# TFTProtoBreakout.net
KiCad netlist of a schematic drawn in EAGLE
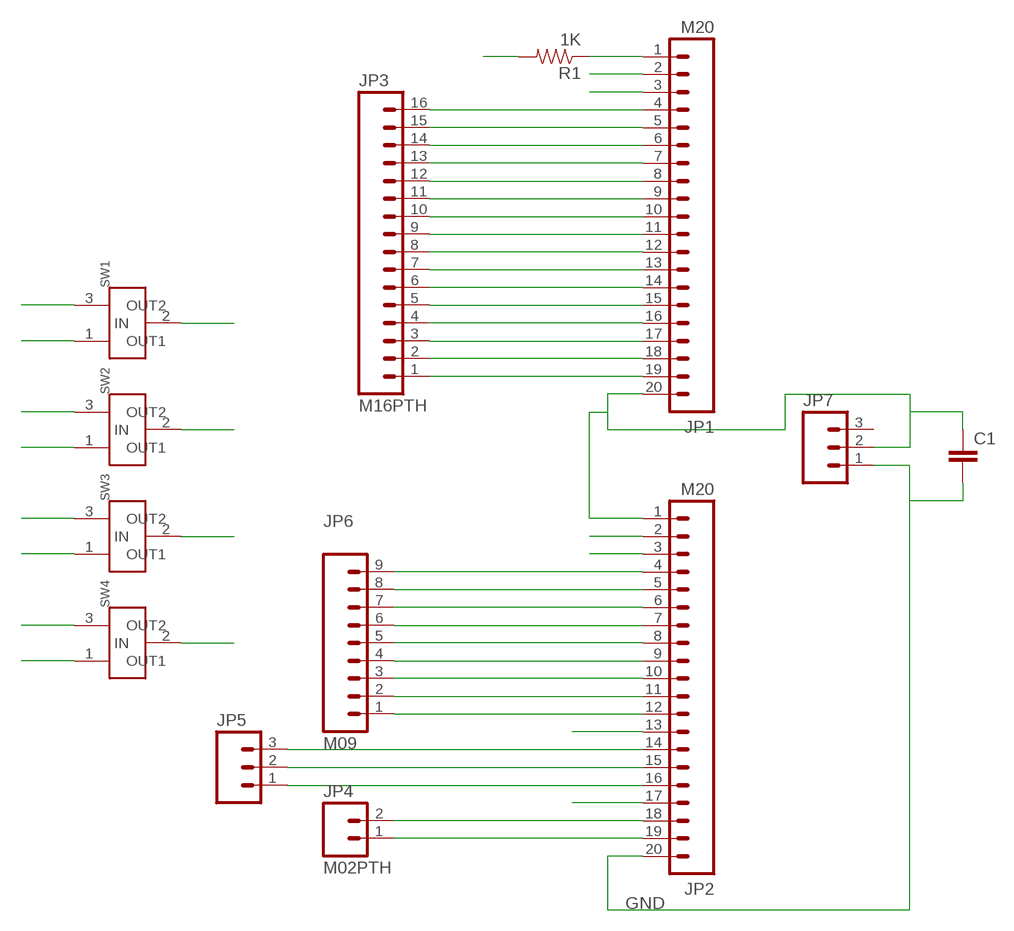
[diagram p0: schematic, sheet 1]

(export (version "E")
  (design (tool "Eeschema 10.0.6"))
  (components
    (comp (ref "C1")
      (value "CAP0805")
      (footprint "eagle-import:0805")
      (libsource (lib "eagle-import") (part "CAP0805"))
    )
    (comp (ref "JP1")
      (value "M20")
      (footprint "eagle-import:1X20")
      (libsource (lib "eagle-import") (part "M20"))
    )
    (comp (ref "JP2")
      (value "M20")
      (footprint "eagle-import:1X20")
      (libsource (lib "eagle-import") (part "M20"))
    )
    (comp (ref "JP3")
      (value "M16PTH")
      (footprint "eagle-import:1X16")
      (libsource (lib "eagle-import") (part "M16PTH"))
    )
    (comp (ref "JP4")
      (value "M02PTH")
      (footprint "eagle-import:1X02")
      (libsource (lib "eagle-import") (part "M02PTH"))
    )
    (comp (ref "JP5")
      (value "M03PTH")
      (footprint "eagle-import:1X03")
      (libsource (lib "eagle-import") (part "M03PTH"))
    )
    (comp (ref "JP6")
      (value "M09")
      (footprint "eagle-import:1X09")
      (libsource (lib "eagle-import") (part "M09"))
    )
    (comp (ref "JP7")
      (value "M03PTH")
      (footprint "eagle-import:1X03")
      (libsource (lib "eagle-import") (part "M03PTH"))
    )
    (comp (ref "R1")
      (value "1K")
      (footprint "eagle-import:0603-RES")
      (libsource (lib "eagle-import") (part "1KOHM1/10W1%(0603)"))
    )
    (comp (ref "SW1")
      (value "PCM12SMTR")
      (footprint "eagle-import:PCM12SMTR")
      (libsource (lib "eagle-import") (part "PCM12SMTR"))
    )
    (comp (ref "SW2")
      (value "PCM12SMTR")
      (footprint "eagle-import:PCM12SMTR")
      (libsource (lib "eagle-import") (part "PCM12SMTR"))
    )
    (comp (ref "SW3")
      (value "PCM12SMTR")
      (footprint "eagle-import:PCM12SMTR")
      (libsource (lib "eagle-import") (part "PCM12SMTR"))
    )
    (comp (ref "SW4")
      (value "PCM12SMTR")
      (footprint "eagle-import:PCM12SMTR")
      (libsource (lib "eagle-import") (part "PCM12SMTR"))
    )
  )
  (nets
    (net (code "1") (name "/GND") (class "Default")
      (node (ref "C1") (pin "2") (pinfunction "2_2") (pintype "passive"))
      (node (ref "JP2") (pin "13") (pinfunction "13_13") (pintype "passive"))
      (node (ref "JP2") (pin "17") (pinfunction "17_17") (pintype "passive"))
      (node (ref "JP2") (pin "20") (pinfunction "20_20") (pintype "passive"))
      (node (ref "JP7") (pin "1") (pinfunction "1_1") (pintype "passive"))
      (node (ref "R1") (pin "2") (pinfunction "2_2") (pintype "passive"))
      (node (ref "SW1") (pin "1") (pinfunction "OUT1_1") (pintype "bidirectional"))
      (node (ref "SW2") (pin "1") (pinfunction "OUT1_1") (pintype "bidirectional"))
      (node (ref "SW3") (pin "1") (pinfunction "OUT1_1") (pintype "bidirectional"))
      (node (ref "SW4") (pin "1") (pinfunction "OUT1_1") (pintype "bidirectional"))
    )
    (net (code "2") (name "/IM0") (class "Default")
      (node (ref "JP1") (pin "2") (pinfunction "2_2") (pintype "passive"))
      (node (ref "SW1") (pin "2") (pinfunction "IN_2") (pintype "bidirectional"))
    )
    (net (code "3") (name "/IM1") (class "Default")
      (node (ref "JP2") (pin "2") (pinfunction "2_2") (pintype "passive"))
      (node (ref "SW2") (pin "2") (pinfunction "IN_2") (pintype "bidirectional"))
    )
    (net (code "4") (name "/IM2") (class "Default")
      (node (ref "JP1") (pin "3") (pinfunction "3_3") (pintype "passive"))
      (node (ref "SW3") (pin "2") (pinfunction "IN_2") (pintype "bidirectional"))
    )
    (net (code "5") (name "/IM3") (class "Default")
      (node (ref "JP2") (pin "3") (pinfunction "3_3") (pintype "passive"))
      (node (ref "SW4") (pin "2") (pinfunction "IN_2") (pintype "bidirectional"))
    )
    (net (code "6") (name "/VCC") (class "Default")
      (node (ref "C1") (pin "1") (pinfunction "1_1") (pintype "passive"))
      (node (ref "JP1") (pin "20") (pinfunction "20_20") (pintype "passive"))
      (node (ref "JP2") (pin "1") (pinfunction "1_1") (pintype "passive"))
      (node (ref "JP7") (pin "2") (pinfunction "2_2") (pintype "passive"))
      (node (ref "SW1") (pin "3") (pinfunction "OUT2_3") (pintype "bidirectional"))
      (node (ref "SW2") (pin "3") (pinfunction "OUT2_3") (pintype "bidirectional"))
      (node (ref "SW3") (pin "3") (pinfunction "OUT2_3") (pintype "bidirectional"))
      (node (ref "SW4") (pin "3") (pinfunction "OUT2_3") (pintype "bidirectional"))
    )
    (net (code "7") (name "Net-(JP1-Pad1)") (class "Default")
      (node (ref "JP1") (pin "1") (pinfunction "1_1") (pintype "passive"))
      (node (ref "R1") (pin "1") (pinfunction "1_1") (pintype "passive"))
    )
    (net (code "8") (name "Net-(JP1-Pad4)") (class "Default")
      (node (ref "JP1") (pin "4") (pinfunction "4_4") (pintype "passive"))
      (node (ref "JP3") (pin "16") (pinfunction "16_16") (pintype "passive"))
    )
    (net (code "9") (name "Net-(JP1-Pad5)") (class "Default")
      (node (ref "JP1") (pin "5") (pinfunction "5_5") (pintype "passive"))
      (node (ref "JP3") (pin "15") (pinfunction "15_15") (pintype "passive"))
    )
    (net (code "10") (name "Net-(JP1-Pad6)") (class "Default")
      (node (ref "JP1") (pin "6") (pinfunction "6_6") (pintype "passive"))
      (node (ref "JP3") (pin "14") (pinfunction "14_14") (pintype "passive"))
    )
    (net (code "11") (name "Net-(JP1-Pad7)") (class "Default")
      (node (ref "JP1") (pin "7") (pinfunction "7_7") (pintype "passive"))
      (node (ref "JP3") (pin "13") (pinfunction "13_13") (pintype "passive"))
    )
    (net (code "12") (name "Net-(JP1-Pad8)") (class "Default")
      (node (ref "JP1") (pin "8") (pinfunction "8_8") (pintype "passive"))
      (node (ref "JP3") (pin "12") (pinfunction "12_12") (pintype "passive"))
    )
    (net (code "13") (name "Net-(JP1-Pad9)") (class "Default")
      (node (ref "JP1") (pin "9") (pinfunction "9_9") (pintype "passive"))
      (node (ref "JP3") (pin "11") (pinfunction "11_11") (pintype "passive"))
    )
    (net (code "14") (name "Net-(JP1-Pad10)") (class "Default")
      (node (ref "JP1") (pin "10") (pinfunction "10_10") (pintype "passive"))
      (node (ref "JP3") (pin "10") (pinfunction "10_10") (pintype "passive"))
    )
    (net (code "15") (name "Net-(JP1-Pad11)") (class "Default")
      (node (ref "JP1") (pin "11") (pinfunction "11_11") (pintype "passive"))
      (node (ref "JP3") (pin "9") (pinfunction "9_9") (pintype "passive"))
    )
    (net (code "16") (name "Net-(JP1-Pad12)") (class "Default")
      (node (ref "JP1") (pin "12") (pinfunction "12_12") (pintype "passive"))
      (node (ref "JP3") (pin "8") (pinfunction "8_8") (pintype "passive"))
    )
    (net (code "17") (name "Net-(JP1-Pad13)") (class "Default")
      (node (ref "JP1") (pin "13") (pinfunction "13_13") (pintype "passive"))
      (node (ref "JP3") (pin "7") (pinfunction "7_7") (pintype "passive"))
    )
    (net (code "18") (name "Net-(JP1-Pad14)") (class "Default")
      (node (ref "JP1") (pin "14") (pinfunction "14_14") (pintype "passive"))
      (node (ref "JP3") (pin "6") (pinfunction "6_6") (pintype "passive"))
    )
    (net (code "19") (name "Net-(JP1-Pad15)") (class "Default")
      (node (ref "JP1") (pin "15") (pinfunction "15_15") (pintype "passive"))
      (node (ref "JP3") (pin "5") (pinfunction "5_5") (pintype "passive"))
    )
    (net (code "20") (name "Net-(JP1-Pad16)") (class "Default")
      (node (ref "JP1") (pin "16") (pinfunction "16_16") (pintype "passive"))
      (node (ref "JP3") (pin "4") (pinfunction "4_4") (pintype "passive"))
    )
    (net (code "21") (name "Net-(JP1-Pad17)") (class "Default")
      (node (ref "JP1") (pin "17") (pinfunction "17_17") (pintype "passive"))
      (node (ref "JP3") (pin "3") (pinfunction "3_3") (pintype "passive"))
    )
    (net (code "22") (name "Net-(JP1-Pad18)") (class "Default")
      (node (ref "JP1") (pin "18") (pinfunction "18_18") (pintype "passive"))
      (node (ref "JP3") (pin "2") (pinfunction "2_2") (pintype "passive"))
    )
    (net (code "23") (name "Net-(JP1-Pad19)") (class "Default")
      (node (ref "JP1") (pin "19") (pinfunction "19_19") (pintype "passive"))
      (node (ref "JP3") (pin "1") (pinfunction "1_1") (pintype "passive"))
    )
    (net (code "24") (name "Net-(JP2-Pad4)") (class "Default")
      (node (ref "JP2") (pin "4") (pinfunction "4_4") (pintype "passive"))
      (node (ref "JP6") (pin "9") (pinfunction "9_9") (pintype "passive"))
    )
    (net (code "25") (name "Net-(JP2-Pad5)") (class "Default")
      (node (ref "JP2") (pin "5") (pinfunction "5_5") (pintype "passive"))
      (node (ref "JP6") (pin "8") (pinfunction "8_8") (pintype "passive"))
    )
    (net (code "26") (name "Net-(JP2-Pad6)") (class "Default")
      (node (ref "JP2") (pin "6") (pinfunction "6_6") (pintype "passive"))
      (node (ref "JP6") (pin "7") (pinfunction "7_7") (pintype "passive"))
    )
    (net (code "27") (name "Net-(JP2-Pad7)") (class "Default")
      (node (ref "JP2") (pin "7") (pinfunction "7_7") (pintype "passive"))
      (node (ref "JP6") (pin "6") (pinfunction "6_6") (pintype "passive"))
    )
    (net (code "28") (name "Net-(JP2-Pad8)") (class "Default")
      (node (ref "JP2") (pin "8") (pinfunction "8_8") (pintype "passive"))
      (node (ref "JP6") (pin "5") (pinfunction "5_5") (pintype "passive"))
    )
    (net (code "29") (name "Net-(JP2-Pad9)") (class "Default")
      (node (ref "JP2") (pin "9") (pinfunction "9_9") (pintype "passive"))
      (node (ref "JP6") (pin "4") (pinfunction "4_4") (pintype "passive"))
    )
    (net (code "30") (name "Net-(JP2-Pad10)") (class "Default")
      (node (ref "JP2") (pin "10") (pinfunction "10_10") (pintype "passive"))
      (node (ref "JP6") (pin "3") (pinfunction "3_3") (pintype "passive"))
    )
    (net (code "31") (name "Net-(JP2-Pad11)") (class "Default")
      (node (ref "JP2") (pin "11") (pinfunction "11_11") (pintype "passive"))
      (node (ref "JP6") (pin "2") (pinfunction "2_2") (pintype "passive"))
    )
    (net (code "32") (name "Net-(JP2-Pad12)") (class "Default")
      (node (ref "JP2") (pin "12") (pinfunction "12_12") (pintype "passive"))
      (node (ref "JP6") (pin "1") (pinfunction "1_1") (pintype "passive"))
    )
    (net (code "33") (name "Net-(JP2-Pad14)") (class "Default")
      (node (ref "JP2") (pin "14") (pinfunction "14_14") (pintype "passive"))
      (node (ref "JP5") (pin "3") (pinfunction "3_3") (pintype "passive"))
    )
    (net (code "34") (name "Net-(JP2-Pad15)") (class "Default")
      (node (ref "JP2") (pin "15") (pinfunction "15_15") (pintype "passive"))
      (node (ref "JP5") (pin "2") (pinfunction "2_2") (pintype "passive"))
    )
    (net (code "35") (name "Net-(JP2-Pad16)") (class "Default")
      (node (ref "JP2") (pin "16") (pinfunction "16_16") (pintype "passive"))
      (node (ref "JP5") (pin "1") (pinfunction "1_1") (pintype "passive"))
    )
    (net (code "36") (name "Net-(JP2-Pad18)") (class "Default")
      (node (ref "JP2") (pin "18") (pinfunction "18_18") (pintype "passive"))
      (node (ref "JP4") (pin "2") (pinfunction "2_2") (pintype "passive"))
    )
    (net (code "37") (name "Net-(JP2-Pad19)") (class "Default")
      (node (ref "JP2") (pin "19") (pinfunction "19_19") (pintype "passive"))
      (node (ref "JP4") (pin "1") (pinfunction "1_1") (pintype "passive"))
    )
    (net (code "38") (name "unconnected-(JP7-Pad3)") (class "Default")
      (node (ref "JP7") (pin "3") (pinfunction "3_3") (pintype "passive"))
    )
  )
)
